# rev1.net
KiCad netlist of a schematic drawn in Altium Designer
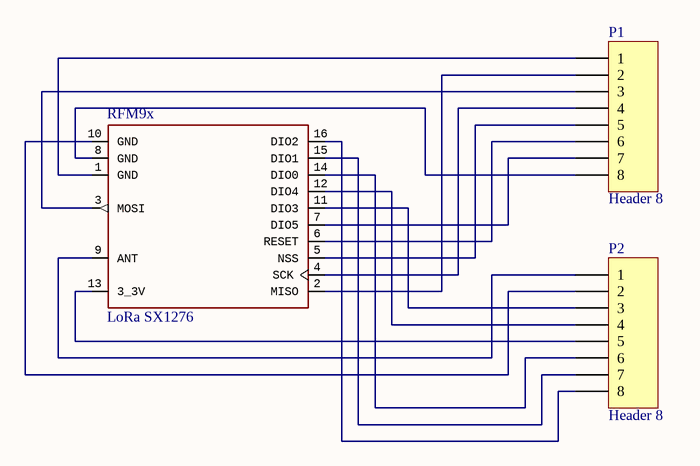
[diagram p0: rev1.SchDoc]

(export (version "E")
  (design (tool "Eeschema 10.0.6"))
  (components
    (comp (ref "P1")
      (value "Header 8")
      (footprint "HDR1X8")
      (description "Header, 8-Pin")
      (fields (field (name "PUBLISHER") "Altium Limited"))
      (libsource (lib "Miscellaneous Connectors") (part "Header 8"))
    )
    (comp (ref "P2")
      (value "Header 8")
      (footprint "HDR1X8")
      (description "Header, 8-Pin")
      (fields (field (name "PUBLISHER") "Altium Limited"))
      (libsource (lib "Miscellaneous Connectors") (part "Header 8"))
    )
    (comp (ref "RFM9x")
      (value "LoRa SX1276")
      (footprint "XCVR_RFM95W-868S2")
      (fields (field (name "MF") "RF") (field (name "MP") "RFM95W-868S2"))
      (libsource (lib "RFM95W-868S2") (part "RFM95W-868S2"))
    )
  )
  (nets
    (net (code "1") (name "Net-(P1-Pad1)") (class "Default")
      (node (ref "P1") (pin "1") (pinfunction "1_1") (pintype "passive"))
      (node (ref "RFM9x") (pin "1") (pinfunction "GND_1") (pintype "power_in"))
    )
    (net (code "2") (name "Net-(P1-Pad8)") (class "Default")
      (node (ref "P1") (pin "8") (pinfunction "8_8") (pintype "passive"))
      (node (ref "RFM9x") (pin "8") (pinfunction "GND_8") (pintype "power_in"))
    )
    (net (code "3") (name "Net-(P2-Pad2)") (class "Default")
      (node (ref "P2") (pin "2") (pinfunction "2_2") (pintype "passive"))
      (node (ref "RFM9x") (pin "10") (pinfunction "GND_10") (pintype "power_in"))
    )
    (net (code "4") (name "Net-(RFM9x-3_3V)") (class "Default")
      (node (ref "P2") (pin "5") (pinfunction "5_5") (pintype "passive"))
      (node (ref "RFM9x") (pin "13") (pinfunction "3_3V_13") (pintype "power_in"))
    )
    (net (code "5") (name "Net-(RFM9x-ANT)") (class "Default")
      (node (ref "P2") (pin "1") (pinfunction "1_1") (pintype "passive"))
      (node (ref "RFM9x") (pin "9") (pinfunction "ANT_9") (pintype "passive"))
    )
    (net (code "6") (name "Net-(RFM9x-DIO0)") (class "Default")
      (node (ref "P2") (pin "6") (pinfunction "6_6") (pintype "passive"))
      (node (ref "RFM9x") (pin "14") (pinfunction "DIO0_14") (pintype "passive"))
    )
    (net (code "7") (name "Net-(RFM9x-DIO1)") (class "Default")
      (node (ref "P2") (pin "7") (pinfunction "7_7") (pintype "passive"))
      (node (ref "RFM9x") (pin "15") (pinfunction "DIO1_15") (pintype "passive"))
    )
    (net (code "8") (name "Net-(RFM9x-DIO2)") (class "Default")
      (node (ref "P2") (pin "8") (pinfunction "8_8") (pintype "passive"))
      (node (ref "RFM9x") (pin "16") (pinfunction "DIO2_16") (pintype "passive"))
    )
    (net (code "9") (name "Net-(RFM9x-DIO3)") (class "Default")
      (node (ref "P2") (pin "3") (pinfunction "3_3") (pintype "passive"))
      (node (ref "RFM9x") (pin "11") (pinfunction "DIO3_11") (pintype "passive"))
    )
    (net (code "10") (name "Net-(RFM9x-DIO4)") (class "Default")
      (node (ref "P2") (pin "4") (pinfunction "4_4") (pintype "passive"))
      (node (ref "RFM9x") (pin "12") (pinfunction "DIO4_12") (pintype "passive"))
    )
    (net (code "11") (name "Net-(RFM9x-DIO5)") (class "Default")
      (node (ref "P1") (pin "7") (pinfunction "7_7") (pintype "passive"))
      (node (ref "RFM9x") (pin "7") (pinfunction "DIO5_7") (pintype "passive"))
    )
    (net (code "12") (name "Net-(RFM9x-MISO)") (class "Default")
      (node (ref "P1") (pin "2") (pinfunction "2_2") (pintype "passive"))
      (node (ref "RFM9x") (pin "2") (pinfunction "MISO_2") (pintype "passive"))
    )
    (net (code "13") (name "Net-(RFM9x-MOSI)") (class "Default")
      (node (ref "P1") (pin "3") (pinfunction "3_3") (pintype "passive"))
      (node (ref "RFM9x") (pin "3") (pinfunction "MOSI_3") (pintype "output"))
    )
    (net (code "14") (name "Net-(RFM9x-NSS)") (class "Default")
      (node (ref "P1") (pin "5") (pinfunction "5_5") (pintype "passive"))
      (node (ref "RFM9x") (pin "5") (pinfunction "NSS_5") (pintype "passive"))
    )
    (net (code "15") (name "Net-(RFM9x-RESET)") (class "Default")
      (node (ref "P1") (pin "6") (pinfunction "6_6") (pintype "passive"))
      (node (ref "RFM9x") (pin "6") (pinfunction "RESET_6") (pintype "passive"))
    )
    (net (code "16") (name "Net-(RFM9x-SCK)") (class "Default")
      (node (ref "P1") (pin "4") (pinfunction "4_4") (pintype "passive"))
      (node (ref "RFM9x") (pin "4") (pinfunction "SCK_4") (pintype "passive"))
    )
  )
)
